# TPS3813.net
KiCad netlist of a schematic drawn in EAGLE
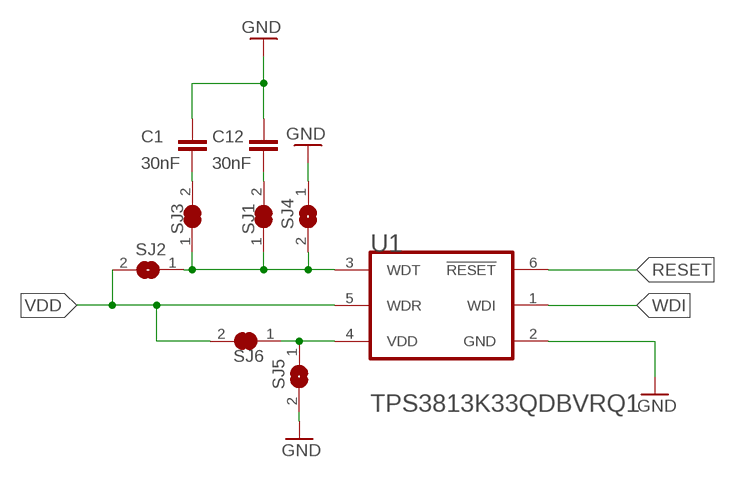
[diagram p0: schematic, sheet 1]

(export (version "E")
  (design (tool "Eeschema 10.0.6"))
  (components
    (comp (ref "C1")
      (value "30nF")
      (footprint "eagle-import:C0603")
      (libsource (lib "eagle-import") (part "C-EUC0603"))
    )
    (comp (ref "C12")
      (value "30nF")
      (footprint "eagle-import:C0603")
      (libsource (lib "eagle-import") (part "C-EUC0603"))
    )
    (comp (ref "SJ1")
      (value "SOLDERJUMPER_CLOSED")
      (footprint "eagle-import:SOLDERJUMPER_CLOSEDWIRE")
      (libsource (lib "eagle-import") (part "SOLDERJUMPER_CLOSED"))
    )
    (comp (ref "SJ2") (value "SJ") (footprint "eagle-import:SJ") (libsource (lib "eagle-import") (part "SJ")))
    (comp (ref "SJ3")
      (value "SOLDERJUMPER_CLOSED")
      (footprint "eagle-import:SOLDERJUMPER_CLOSEDWIRE")
      (libsource (lib "eagle-import") (part "SOLDERJUMPER_CLOSED"))
    )
    (comp (ref "SJ4") (value "SJ") (footprint "eagle-import:SJ") (libsource (lib "eagle-import") (part "SJ")))
    (comp (ref "SJ5") (value "SJ") (footprint "eagle-import:SJ") (libsource (lib "eagle-import") (part "SJ")))
    (comp (ref "SJ6")
      (value "SOLDERJUMPER_CLOSED")
      (footprint "eagle-import:SOLDERJUMPER_CLOSEDWIRE")
      (libsource (lib "eagle-import") (part "SOLDERJUMPER_CLOSED"))
    )
    (comp (ref "U1")
      (value "TEXAS_INSTRUMENTS_TPS3813K33QDBVRQ1TEXAS_INSTRUMENTS_TPS3813K33QDBVRQ1_0_2")
      (footprint "eagle-import:TEXAS_INSTRUMENTS_TPS3813K33QDBVRQ1_2")
      (fields (field (name "MF") "Texas Instruments") (field (name "MPN") "TPS3813K33QDBVRQ1"))
      (libsource (lib "eagle-import") (part "TEXAS_INSTRUMENTS_TPS3813K33QDBVRQ1TEXAS_INSTRUMENTS_TPS3813K33QDBVRQ1_0_2"))
    )
  )
  (nets
    (net (code "1") (name "GND") (class "Default")
      (node (ref "C1") (pin "1") (pinfunction "1_1") (pintype "passive"))
      (node (ref "C12") (pin "1") (pinfunction "1_1") (pintype "passive"))
      (node (ref "SJ4") (pin "1") (pinfunction "1_1") (pintype "passive"))
      (node (ref "SJ5") (pin "2") (pinfunction "2_2") (pintype "passive"))
      (node (ref "U1") (pin "2") (pinfunction "GND_2") (pintype "power_in"))
    )
    (net (code "2") (name "Net-(C1-Pad2)") (class "Default")
      (node (ref "C1") (pin "2") (pinfunction "2_2") (pintype "passive"))
      (node (ref "SJ3") (pin "2") (pinfunction "2_2") (pintype "passive"))
    )
    (net (code "3") (name "Net-(C12-Pad2)") (class "Default")
      (node (ref "C12") (pin "2") (pinfunction "2_2") (pintype "passive"))
      (node (ref "SJ1") (pin "2") (pinfunction "2_2") (pintype "passive"))
    )
    (net (code "4") (name "Net-(U1-VDD)") (class "Default")
      (node (ref "SJ5") (pin "1") (pinfunction "1_1") (pintype "passive"))
      (node (ref "SJ6") (pin "1") (pinfunction "1_1") (pintype "passive"))
      (node (ref "U1") (pin "4") (pinfunction "VDD_4") (pintype "power_in"))
    )
    (net (code "5") (name "Net-(U1-WDT)") (class "Default")
      (node (ref "SJ1") (pin "1") (pinfunction "1_1") (pintype "passive"))
      (node (ref "SJ2") (pin "1") (pinfunction "1_1") (pintype "passive"))
      (node (ref "SJ3") (pin "1") (pinfunction "1_1") (pintype "passive"))
      (node (ref "SJ4") (pin "2") (pinfunction "2_2") (pintype "passive"))
      (node (ref "U1") (pin "3") (pinfunction "WDT_3") (pintype "input"))
    )
    (net (code "6") (name "RESET") (class "Default")
      (node (ref "U1") (pin "6") (pinfunction "~{RESET}_6") (pintype "open_collector"))
    )
    (net (code "7") (name "VDD") (class "Default")
      (node (ref "SJ2") (pin "2") (pinfunction "2_2") (pintype "passive"))
      (node (ref "SJ6") (pin "2") (pinfunction "2_2") (pintype "passive"))
      (node (ref "U1") (pin "5") (pinfunction "WDR_5") (pintype "input"))
    )
    (net (code "8") (name "WDI") (class "Default")
      (node (ref "U1") (pin "1") (pinfunction "WDI_1") (pintype "input"))
    )
  )
)
